# MCU_And_Peripherals.net
KiCad netlist of a schematic drawn in Altium Designer
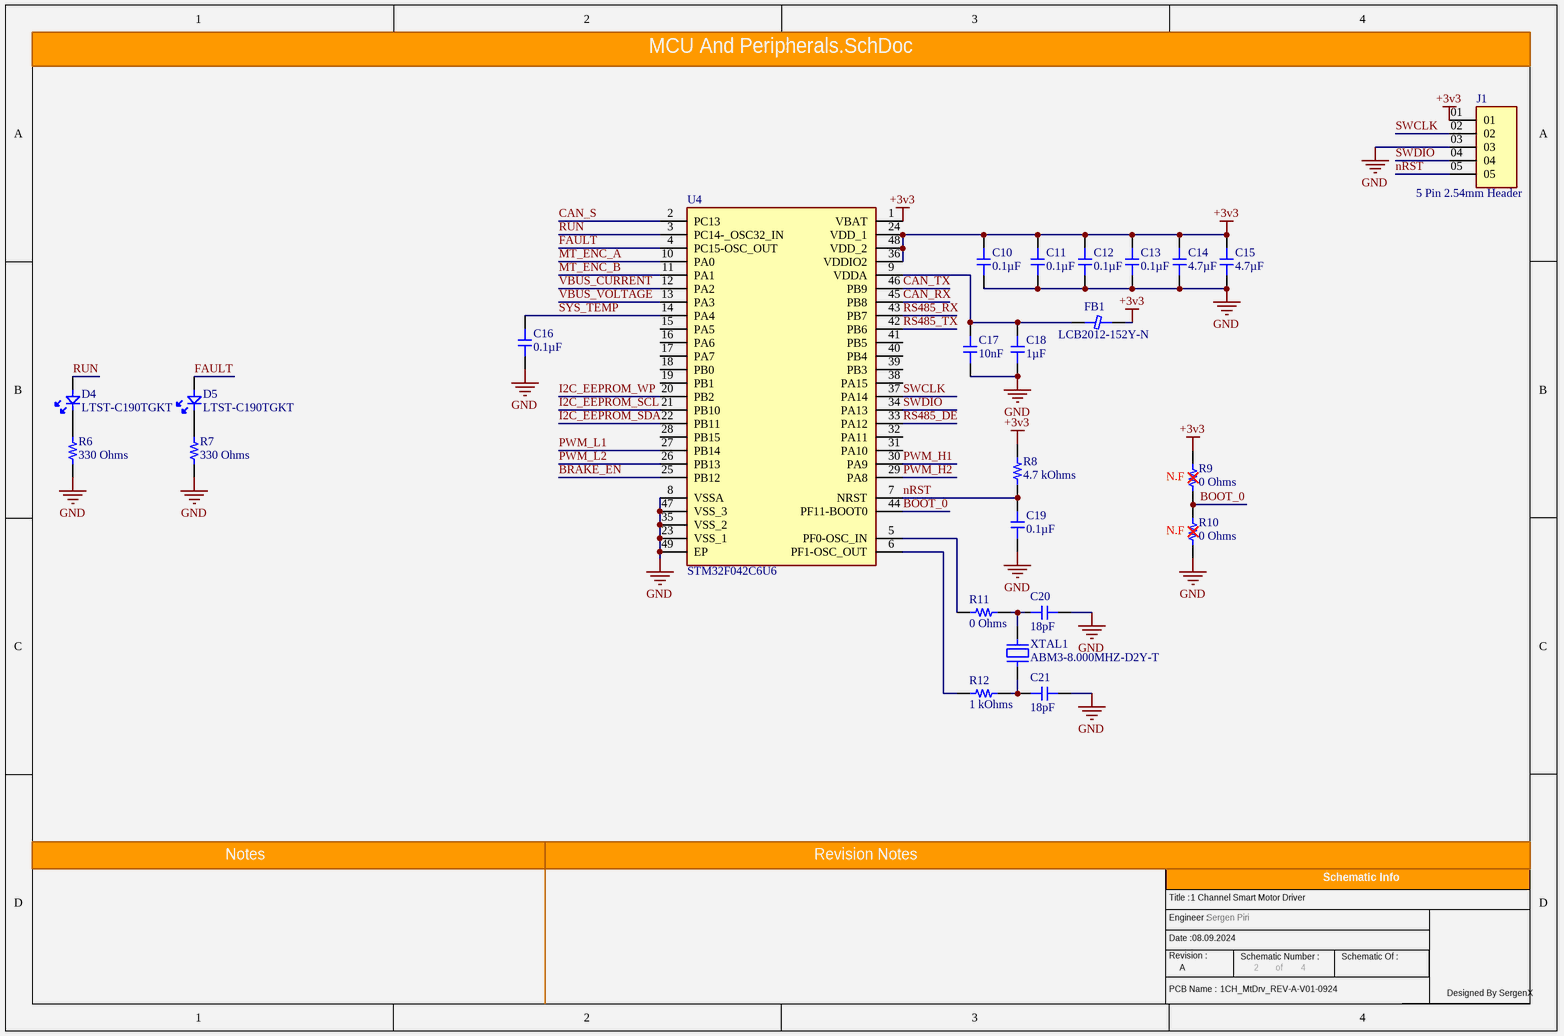
[diagram p0: MCU And Peripherals.SchDoc]

(export (version "E")
  (design (tool "Eeschema 10.0.6"))
  (components
    (comp (ref "C10")
      (value "0.1µF")
      (footprint "0603_Footprint")
      (description "0.1uF 0603 Surface Capacitor")
      (libsource (lib "MainLibrary") (part "0.1uF 0603 Surface Capacitor"))
    )
    (comp (ref "C11")
      (value "0.1µF")
      (footprint "0603_Footprint")
      (description "0.1uF 0603 Surface Capacitor")
      (libsource (lib "MainLibrary") (part "0.1uF 0603 Surface Capacitor"))
    )
    (comp (ref "C12")
      (value "0.1µF")
      (footprint "0603_Footprint")
      (description "0.1uF 0603 Surface Capacitor")
      (libsource (lib "MainLibrary") (part "0.1uF 0603 Surface Capacitor"))
    )
    (comp (ref "C13")
      (value "0.1µF")
      (footprint "0603_Footprint")
      (description "0.1uF 0603 Surface Capacitor")
      (libsource (lib "MainLibrary") (part "0.1uF 0603 Surface Capacitor"))
    )
    (comp (ref "C14")
      (value "4.7µF")
      (footprint "0603_Footprint")
      (description "4.7uF 0603 Surface Capacitor")
      (libsource (lib "MainLibrary") (part "4.7uF 0603 Surface Capacitor"))
    )
    (comp (ref "C15")
      (value "4.7µF")
      (footprint "0603_Footprint")
      (description "4.7uF 0603 Surface Capacitor")
      (libsource (lib "MainLibrary") (part "4.7uF 0603 Surface Capacitor"))
    )
    (comp (ref "C16")
      (value "0.1µF")
      (footprint "0603_Footprint")
      (description "0.1uF 0603 Surface Capacitor")
      (libsource (lib "MainLibrary") (part "0.1uF 0603 Surface Capacitor"))
    )
    (comp (ref "C17")
      (value "10nF")
      (footprint "0603_Footprint")
      (description "10nF 0603 Surface Capacitor")
      (libsource (lib "MainLibrary") (part "10nF 0603 Surface Capacitor"))
    )
    (comp (ref "C18")
      (value "1µF")
      (footprint "0603_Footprint")
      (description "1uF 0603 Surface Capacitor")
      (libsource (lib "MainLibrary") (part "1uF 0603 Surface Capacitor"))
    )
    (comp (ref "C19")
      (value "0.1µF")
      (footprint "0603_Footprint")
      (description "0.1uF 0603 Surface Capacitor")
      (libsource (lib "MainLibrary") (part "0.1uF 0603 Surface Capacitor"))
    )
    (comp (ref "C20")
      (value "18pF")
      (footprint "0603_Footprint")
      (description "18pF 0603 Surface Capacitor")
      (libsource (lib "MainLibrary") (part "18pF 0603 Surface Capacitor"))
    )
    (comp (ref "C21")
      (value "18pF")
      (footprint "0603_Footprint")
      (description "18pF 0603 Surface Capacitor")
      (libsource (lib "MainLibrary") (part "18pF 0603 Surface Capacitor"))
    )
    (comp (ref "D4")
      (value "LTST-C190TGKT")
      (footprint "LEDC1608X80N")
      (description "20mA Generic 0603 Led SMD")
      (fields
        (field (name "MANUFACTURER_PART_NUMBER") "LTST-C190KRKT")
        (field (name "MOUSER PART NUMBER") "859-LTST-C190KRKT")
      )
      (libsource (lib "MainLibrary") (part "LTST-C190TGKT"))
    )
    (comp (ref "D5")
      (value "LTST-C190TGKT")
      (footprint "LEDC1608X80N")
      (description "20mA Generic 0603 Led SMD")
      (fields
        (field (name "MANUFACTURER_PART_NUMBER") "LTST-C190KRKT")
        (field (name "MOUSER PART NUMBER") "859-LTST-C190KRKT")
      )
      (libsource (lib "MainLibrary") (part "LTST-C190TGKT"))
    )
    (comp (ref "FB1")
      (value "LCB2012-152Y-N")
      (footprint "Inductor-0805")
      (description "Ferrite Bead 1A 0805 SMD")
      (libsource (lib "MainLibrary") (part "LCB2012-152Y-N"))
    )
    (comp (ref "J1")
      (value "5 Pin 2.54mm Header")
      (footprint "5PIN_254MM")
      (description "Generic 2.54MM 5 Pin Header")
      (fields (field (name "MP") "MTSW-105-09-G-S-480"))
      (libsource (lib "MainLibrary") (part "5 Pin 2.54mm Header"))
    )
    (comp (ref "R6")
      (value "330 Ohms")
      (footprint "0603_RES")
      (description "330 Ohm 0603")
      (libsource (lib "MainLibrary") (part "330 Ohm 0603"))
    )
    (comp (ref "R7")
      (value "330 Ohms")
      (footprint "0603_RES")
      (description "330 Ohm 0603")
      (libsource (lib "MainLibrary") (part "330 Ohm 0603"))
    )
    (comp (ref "R8")
      (value "4.7 kOhms")
      (footprint "0603_RES")
      (description "4.7 kOhms 0603")
      (libsource (lib "MainLibrary") (part "4.7 kOhms 0603"))
    )
    (comp (ref "R9")
      (value "0 Ohms")
      (footprint "0603_RES")
      (description "0 Ohm 0603")
      (libsource (lib "MainLibrary") (part "0 Ohm 0603"))
    )
    (comp (ref "R10")
      (value "0 Ohms")
      (footprint "0603_RES")
      (description "0 Ohm 0603")
      (libsource (lib "MainLibrary") (part "0 Ohm 0603"))
    )
    (comp (ref "R11")
      (value "0 Ohms")
      (footprint "0603_RES")
      (description "0 Ohm 0603")
      (libsource (lib "MainLibrary") (part "0 Ohm 0603"))
    )
    (comp (ref "R12")
      (value "1 kOhms")
      (footprint "0603_RES")
      (description "1 kOhms 0603")
      (libsource (lib "MainLibrary") (part "1 kOhms 0603"))
    )
    (comp (ref "U4")
      (value "STM32F042C6U6")
      (footprint "QFN50P700X700X60-49N")
      (description "STMICROELECTRONICS - STM32F042C6U6 - MCU, ARM CORTEX-M0, 48MHZ, UFQFPN-48")
      (fields (field (name "MOUSER PART NUMBER") "511-STM32F042C6U6"))
      (libsource (lib "MainLibrary") (part "STM32F042C6U6"))
    )
    (comp (ref "XTAL1")
      (value "ABM3-8.000MHZ-D2Y-T")
      (footprint "ABM3")
      (description "8MHz 2 Pin SMD Crystal")
      (fields (field (name "MOUSER PART NUMBER") "815-ABM3-8-D2Y-T"))
      (libsource (lib "MainLibrary") (part "ABM3-8.000MHZ-D2Y-T"))
    )
  )
  (nets
    (net (code "1") (name "+3v3") (class "Default")
      (node (ref "C10") (pin "1") (pinfunction "1_1") (pintype "passive"))
      (node (ref "C11") (pin "1") (pinfunction "1_1") (pintype "passive"))
      (node (ref "C12") (pin "1") (pinfunction "1_1") (pintype "passive"))
      (node (ref "C13") (pin "1") (pinfunction "1_1") (pintype "passive"))
      (node (ref "C14") (pin "1") (pinfunction "1_1") (pintype "passive"))
      (node (ref "C15") (pin "1") (pinfunction "1_1") (pintype "passive"))
      (node (ref "FB1") (pin "2") (pinfunction "2_2") (pintype "passive"))
      (node (ref "J1") (pin "01") (pinfunction "01_01") (pintype "passive"))
      (node (ref "R8") (pin "2") (pinfunction "2_2") (pintype "passive"))
      (node (ref "R9") (pin "2") (pinfunction "2_2") (pintype "passive"))
      (node (ref "U4") (pin "1") (pinfunction "VBAT_1") (pintype "passive"))
      (node (ref "U4") (pin "24") (pinfunction "VDD_1_24") (pintype "passive"))
      (node (ref "U4") (pin "36") (pinfunction "VDDIO2_36") (pintype "passive"))
      (node (ref "U4") (pin "48") (pinfunction "VDD_2_48") (pintype "passive"))
    )
    (net (code "2") (name "/BOOT_0") (class "Default")
      (node (ref "R10") (pin "2") (pinfunction "2_2") (pintype "passive"))
      (node (ref "R9") (pin "1") (pinfunction "1_1") (pintype "passive"))
      (node (ref "U4") (pin "44") (pinfunction "PF11-BOOT0_44") (pintype "passive"))
    )
    (net (code "3") (name "/BRAKE_EN") (class "Default")
      (node (ref "U4") (pin "25") (pinfunction "PB12_25") (pintype "passive"))
    )
    (net (code "4") (name "/CAN_RX") (class "Default")
      (node (ref "U4") (pin "45") (pinfunction "PB8_45") (pintype "passive"))
    )
    (net (code "5") (name "/CAN_S") (class "Default")
      (node (ref "U4") (pin "2") (pinfunction "PC13_2") (pintype "passive"))
    )
    (net (code "6") (name "/CAN_TX") (class "Default")
      (node (ref "U4") (pin "46") (pinfunction "PB9_46") (pintype "passive"))
    )
    (net (code "7") (name "/FAULT") (class "Default")
      (node (ref "D5") (pin "2") (pinfunction "A_2") (pintype "passive"))
      (node (ref "U4") (pin "4") (pinfunction "PC15-OSC_OUT_4") (pintype "passive"))
    )
    (net (code "8") (name "/I2C_EEPROM_SCL") (class "Default")
      (node (ref "U4") (pin "21") (pinfunction "PB10_21") (pintype "passive"))
    )
    (net (code "9") (name "/I2C_EEPROM_SDA") (class "Default")
      (node (ref "U4") (pin "22") (pinfunction "PB11_22") (pintype "passive"))
    )
    (net (code "10") (name "/I2C_EEPROM_WP") (class "Default")
      (node (ref "U4") (pin "20") (pinfunction "PB2_20") (pintype "passive"))
    )
    (net (code "11") (name "/MT_ENC_A") (class "Default")
      (node (ref "U4") (pin "10") (pinfunction "PA0_10") (pintype "passive"))
    )
    (net (code "12") (name "/MT_ENC_B") (class "Default")
      (node (ref "U4") (pin "11") (pinfunction "PA1_11") (pintype "passive"))
    )
    (net (code "13") (name "/PWM_H1") (class "Default")
      (node (ref "U4") (pin "30") (pinfunction "PA9_30") (pintype "passive"))
    )
    (net (code "14") (name "/PWM_H2") (class "Default")
      (node (ref "U4") (pin "29") (pinfunction "PA8_29") (pintype "passive"))
    )
    (net (code "15") (name "/PWM_L1") (class "Default")
      (node (ref "U4") (pin "27") (pinfunction "PB14_27") (pintype "passive"))
    )
    (net (code "16") (name "/PWM_L2") (class "Default")
      (node (ref "U4") (pin "26") (pinfunction "PB13_26") (pintype "passive"))
    )
    (net (code "17") (name "/RS485_DE") (class "Default")
      (node (ref "U4") (pin "33") (pinfunction "PA12_33") (pintype "passive"))
    )
    (net (code "18") (name "/RS485_RX") (class "Default")
      (node (ref "U4") (pin "43") (pinfunction "PB7_43") (pintype "passive"))
    )
    (net (code "19") (name "/RS485_TX") (class "Default")
      (node (ref "U4") (pin "42") (pinfunction "PB6_42") (pintype "passive"))
    )
    (net (code "20") (name "/RUN") (class "Default")
      (node (ref "D4") (pin "2") (pinfunction "A_2") (pintype "passive"))
      (node (ref "U4") (pin "3") (pinfunction "PC14-_OSC32_IN_3") (pintype "passive"))
    )
    (net (code "21") (name "/SWCLK") (class "Default")
      (node (ref "J1") (pin "02") (pinfunction "02_02") (pintype "passive"))
      (node (ref "U4") (pin "37") (pinfunction "PA14_37") (pintype "passive"))
    )
    (net (code "22") (name "/SWDIO") (class "Default")
      (node (ref "J1") (pin "04") (pinfunction "04_04") (pintype "passive"))
      (node (ref "U4") (pin "34") (pinfunction "PA13_34") (pintype "passive"))
    )
    (net (code "23") (name "/SYS_TEMP") (class "Default")
      (node (ref "C16") (pin "1") (pinfunction "1_1") (pintype "passive"))
      (node (ref "U4") (pin "14") (pinfunction "PA4_14") (pintype "passive"))
    )
    (net (code "24") (name "/VBUS_CURRENT") (class "Default")
      (node (ref "U4") (pin "12") (pinfunction "PA2_12") (pintype "passive"))
    )
    (net (code "25") (name "/VBUS_VOLTAGE") (class "Default")
      (node (ref "U4") (pin "13") (pinfunction "PA3_13") (pintype "passive"))
    )
    (net (code "26") (name "/nRST") (class "Default")
      (node (ref "C19") (pin "2") (pinfunction "2_2") (pintype "passive"))
      (node (ref "J1") (pin "05") (pinfunction "05_05") (pintype "passive"))
      (node (ref "R8") (pin "1") (pinfunction "1_1") (pintype "passive"))
      (node (ref "U4") (pin "7") (pinfunction "NRST_7") (pintype "passive"))
    )
    (net (code "27") (name "GND") (class "Default")
      (node (ref "C10") (pin "2") (pinfunction "2_2") (pintype "passive"))
      (node (ref "C11") (pin "2") (pinfunction "2_2") (pintype "passive"))
      (node (ref "C12") (pin "2") (pinfunction "2_2") (pintype "passive"))
      (node (ref "C13") (pin "2") (pinfunction "2_2") (pintype "passive"))
      (node (ref "C14") (pin "2") (pinfunction "2_2") (pintype "passive"))
      (node (ref "C15") (pin "2") (pinfunction "2_2") (pintype "passive"))
      (node (ref "C16") (pin "2") (pinfunction "2_2") (pintype "passive"))
      (node (ref "C17") (pin "2") (pinfunction "2_2") (pintype "passive"))
      (node (ref "C18") (pin "2") (pinfunction "2_2") (pintype "passive"))
      (node (ref "C19") (pin "1") (pinfunction "1_1") (pintype "passive"))
      (node (ref "C20") (pin "2") (pinfunction "2_2") (pintype "passive"))
      (node (ref "C21") (pin "2") (pinfunction "2_2") (pintype "passive"))
      (node (ref "J1") (pin "03") (pinfunction "03_03") (pintype "passive"))
      (node (ref "R10") (pin "1") (pinfunction "1_1") (pintype "passive"))
      (node (ref "R6") (pin "1") (pinfunction "1_1") (pintype "passive"))
      (node (ref "R7") (pin "1") (pinfunction "1_1") (pintype "passive"))
      (node (ref "U4") (pin "23") (pinfunction "VSS_1_23") (pintype "passive"))
      (node (ref "U4") (pin "35") (pinfunction "VSS_2_35") (pintype "passive"))
      (node (ref "U4") (pin "47") (pinfunction "VSS_3_47") (pintype "passive"))
      (node (ref "U4") (pin "49") (pinfunction "EP_49") (pintype "passive"))
      (node (ref "U4") (pin "8") (pinfunction "VSSA_8") (pintype "passive"))
    )
    (net (code "28") (name "Net-(C20-Pad1)") (class "Default")
      (node (ref "C20") (pin "1") (pinfunction "1_1") (pintype "passive"))
      (node (ref "R11") (pin "2") (pinfunction "2_2") (pintype "passive"))
      (node (ref "XTAL1") (pin "2") (pinfunction "2_2") (pintype "passive"))
    )
    (net (code "29") (name "Net-(C21-Pad1)") (class "Default")
      (node (ref "C21") (pin "1") (pinfunction "1_1") (pintype "passive"))
      (node (ref "R12") (pin "2") (pinfunction "2_2") (pintype "passive"))
      (node (ref "XTAL1") (pin "1") (pinfunction "1_1") (pintype "passive"))
    )
    (net (code "30") (name "Net-(D4-K)") (class "Default")
      (node (ref "D4") (pin "1") (pinfunction "K_1") (pintype "passive"))
      (node (ref "R6") (pin "2") (pinfunction "2_2") (pintype "passive"))
    )
    (net (code "31") (name "Net-(D5-K)") (class "Default")
      (node (ref "D5") (pin "1") (pinfunction "K_1") (pintype "passive"))
      (node (ref "R7") (pin "2") (pinfunction "2_2") (pintype "passive"))
    )
    (net (code "32") (name "Net-(U4-PF0-OSC_IN)") (class "Default")
      (node (ref "R11") (pin "1") (pinfunction "1_1") (pintype "passive"))
      (node (ref "U4") (pin "5") (pinfunction "PF0-OSC_IN_5") (pintype "passive"))
    )
    (net (code "33") (name "Net-(U4-PF1-OSC_OUT)") (class "Default")
      (node (ref "R12") (pin "1") (pinfunction "1_1") (pintype "passive"))
      (node (ref "U4") (pin "6") (pinfunction "PF1-OSC_OUT_6") (pintype "passive"))
    )
    (net (code "34") (name "Net-(U4-VDDA)") (class "Default")
      (node (ref "C17") (pin "1") (pinfunction "1_1") (pintype "passive"))
      (node (ref "C18") (pin "1") (pinfunction "1_1") (pintype "passive"))
      (node (ref "FB1") (pin "1") (pinfunction "1_1") (pintype "passive"))
      (node (ref "U4") (pin "9") (pinfunction "VDDA_9") (pintype "passive"))
    )
    (net (code "35") (name "unconnected-(U4-PA5-Pad15)") (class "Default")
      (node (ref "U4") (pin "15") (pinfunction "PA5_15") (pintype "passive"))
    )
    (net (code "36") (name "unconnected-(U4-PA6-Pad16)") (class "Default")
      (node (ref "U4") (pin "16") (pinfunction "PA6_16") (pintype "passive"))
    )
    (net (code "37") (name "unconnected-(U4-PA7-Pad17)") (class "Default")
      (node (ref "U4") (pin "17") (pinfunction "PA7_17") (pintype "passive"))
    )
    (net (code "38") (name "unconnected-(U4-PA10-Pad31)") (class "Default")
      (node (ref "U4") (pin "31") (pinfunction "PA10_31") (pintype "passive"))
    )
    (net (code "39") (name "unconnected-(U4-PA11-Pad32)") (class "Default")
      (node (ref "U4") (pin "32") (pinfunction "PA11_32") (pintype "passive"))
    )
    (net (code "40") (name "unconnected-(U4-PA15-Pad38)") (class "Default")
      (node (ref "U4") (pin "38") (pinfunction "PA15_38") (pintype "passive"))
    )
    (net (code "41") (name "unconnected-(U4-PB0-Pad18)") (class "Default")
      (node (ref "U4") (pin "18") (pinfunction "PB0_18") (pintype "passive"))
    )
    (net (code "42") (name "unconnected-(U4-PB1-Pad19)") (class "Default")
      (node (ref "U4") (pin "19") (pinfunction "PB1_19") (pintype "passive"))
    )
    (net (code "43") (name "unconnected-(U4-PB3-Pad39)") (class "Default")
      (node (ref "U4") (pin "39") (pinfunction "PB3_39") (pintype "passive"))
    )
    (net (code "44") (name "unconnected-(U4-PB4-Pad40)") (class "Default")
      (node (ref "U4") (pin "40") (pinfunction "PB4_40") (pintype "passive"))
    )
    (net (code "45") (name "unconnected-(U4-PB5-Pad41)") (class "Default")
      (node (ref "U4") (pin "41") (pinfunction "PB5_41") (pintype "passive"))
    )
    (net (code "46") (name "unconnected-(U4-PB15-Pad28)") (class "Default")
      (node (ref "U4") (pin "28") (pinfunction "PB15_28") (pintype "passive"))
    )
  )
)
